# DMX_1_0.net
KiCad netlist of a schematic drawn in EAGLE
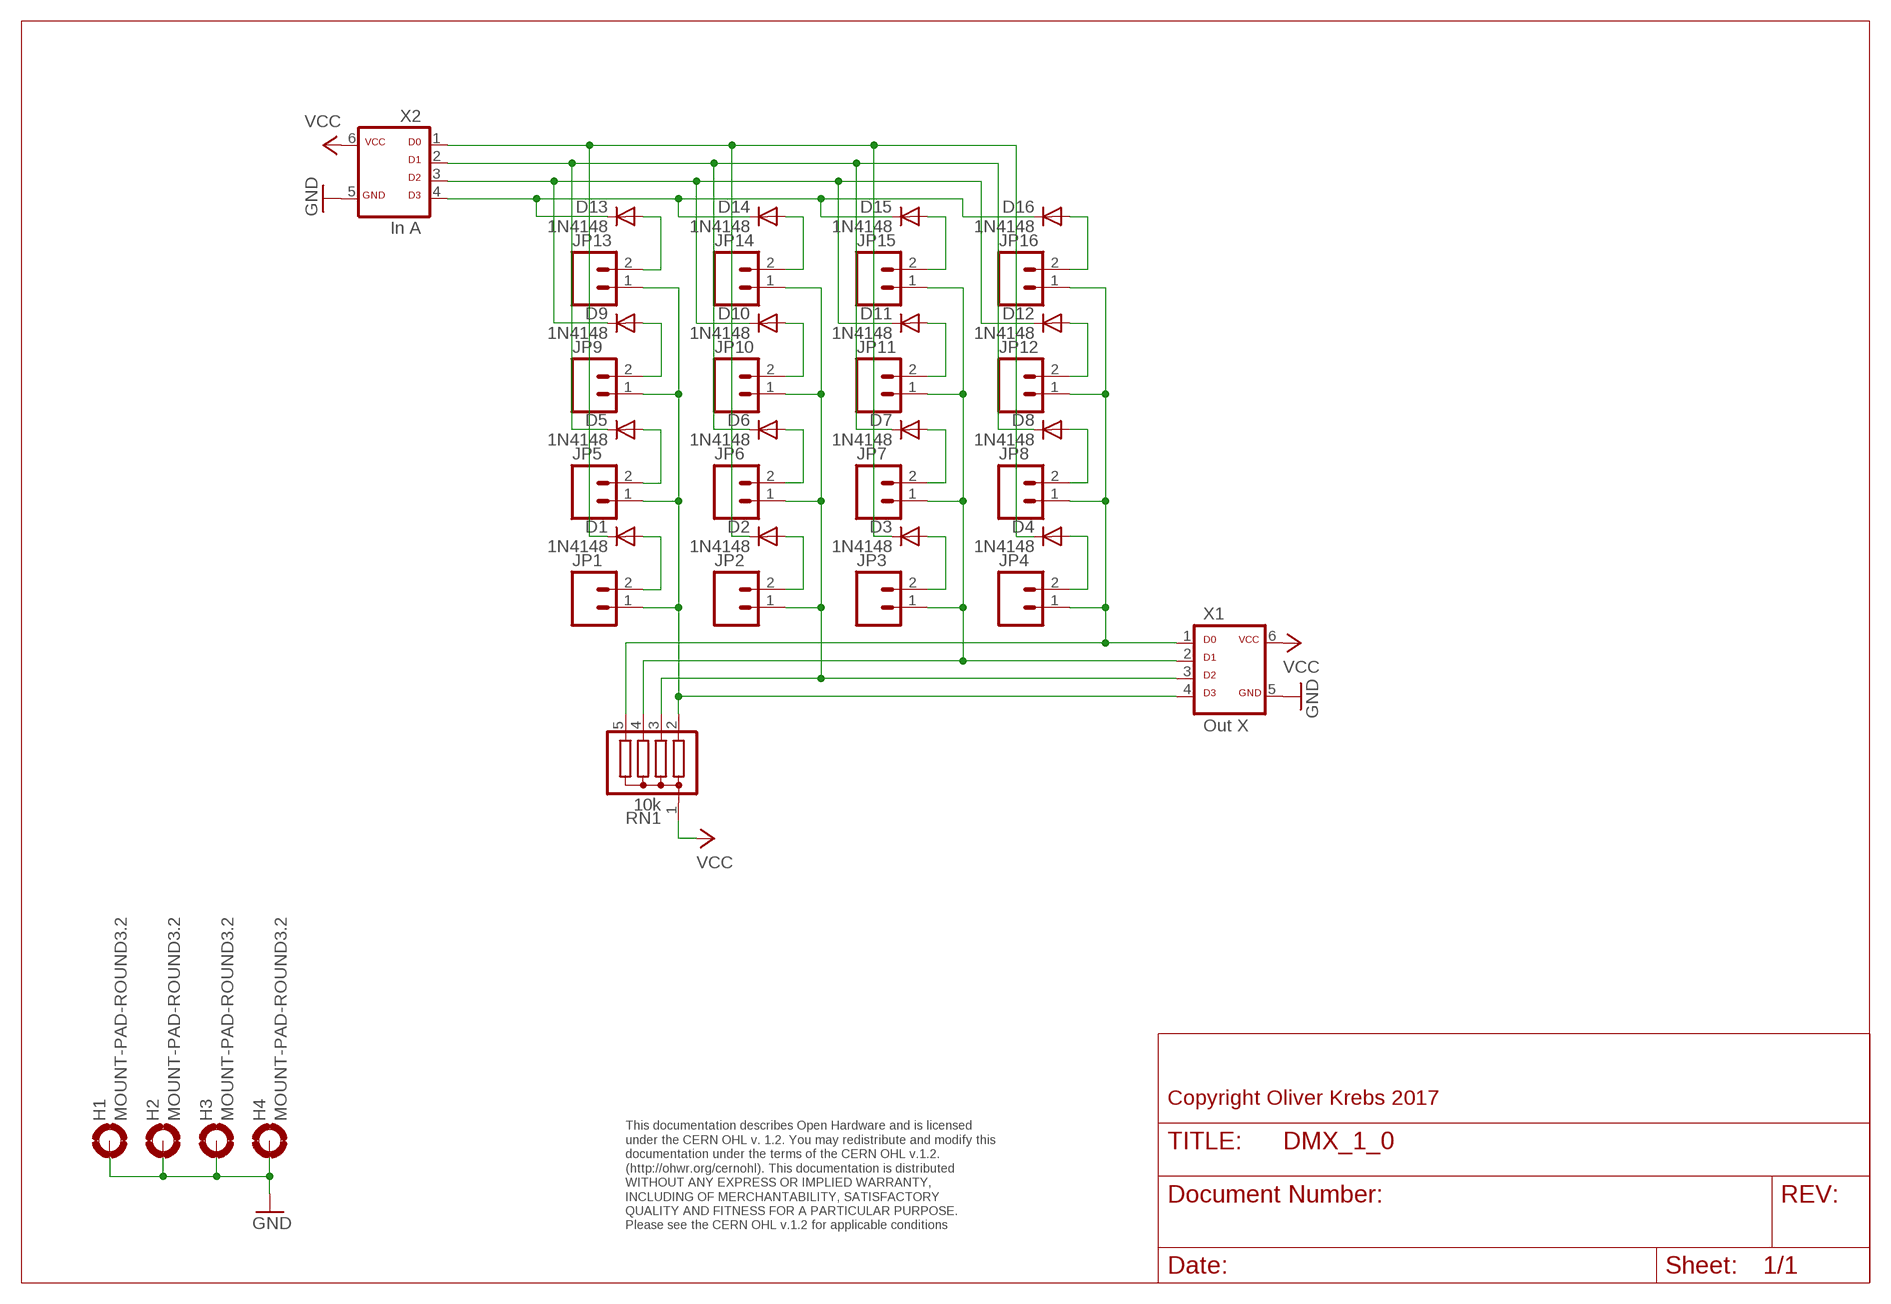
[diagram p0: schematic, sheet 1]

(export (version "E")
  (design (tool "Eeschema 10.0.6"))
  (components
    (comp (ref "D1")
      (value "1N4148")
      (footprint "eagle-import:DO35-7")
      (libsource (lib "eagle-import") (part "1N4148DO35-7"))
    )
    (comp (ref "D2")
      (value "1N4148")
      (footprint "eagle-import:DO35-7")
      (libsource (lib "eagle-import") (part "1N4148DO35-7"))
    )
    (comp (ref "D3")
      (value "1N4148")
      (footprint "eagle-import:DO35-7")
      (libsource (lib "eagle-import") (part "1N4148DO35-7"))
    )
    (comp (ref "D4")
      (value "1N4148")
      (footprint "eagle-import:DO35-7")
      (libsource (lib "eagle-import") (part "1N4148DO35-7"))
    )
    (comp (ref "D5")
      (value "1N4148")
      (footprint "eagle-import:DO35-7")
      (libsource (lib "eagle-import") (part "1N4148DO35-7"))
    )
    (comp (ref "D6")
      (value "1N4148")
      (footprint "eagle-import:DO35-7")
      (libsource (lib "eagle-import") (part "1N4148DO35-7"))
    )
    (comp (ref "D7")
      (value "1N4148")
      (footprint "eagle-import:DO35-7")
      (libsource (lib "eagle-import") (part "1N4148DO35-7"))
    )
    (comp (ref "D8")
      (value "1N4148")
      (footprint "eagle-import:DO35-7")
      (libsource (lib "eagle-import") (part "1N4148DO35-7"))
    )
    (comp (ref "D9")
      (value "1N4148")
      (footprint "eagle-import:DO35-7")
      (libsource (lib "eagle-import") (part "1N4148DO35-7"))
    )
    (comp (ref "D10")
      (value "1N4148")
      (footprint "eagle-import:DO35-7")
      (libsource (lib "eagle-import") (part "1N4148DO35-7"))
    )
    (comp (ref "D11")
      (value "1N4148")
      (footprint "eagle-import:DO35-7")
      (libsource (lib "eagle-import") (part "1N4148DO35-7"))
    )
    (comp (ref "D12")
      (value "1N4148")
      (footprint "eagle-import:DO35-7")
      (libsource (lib "eagle-import") (part "1N4148DO35-7"))
    )
    (comp (ref "D13")
      (value "1N4148")
      (footprint "eagle-import:DO35-7")
      (libsource (lib "eagle-import") (part "1N4148DO35-7"))
    )
    (comp (ref "D14")
      (value "1N4148")
      (footprint "eagle-import:DO35-7")
      (libsource (lib "eagle-import") (part "1N4148DO35-7"))
    )
    (comp (ref "D15")
      (value "1N4148")
      (footprint "eagle-import:DO35-7")
      (libsource (lib "eagle-import") (part "1N4148DO35-7"))
    )
    (comp (ref "D16")
      (value "1N4148")
      (footprint "eagle-import:DO35-7")
      (libsource (lib "eagle-import") (part "1N4148DO35-7"))
    )
    (comp (ref "H1")
      (value "MOUNT-PAD-ROUND3.2")
      (footprint "eagle-import:3,2-PAD")
      (libsource (lib "eagle-import") (part "MOUNT-PAD-ROUND3.2"))
    )
    (comp (ref "H2")
      (value "MOUNT-PAD-ROUND3.2")
      (footprint "eagle-import:3,2-PAD")
      (libsource (lib "eagle-import") (part "MOUNT-PAD-ROUND3.2"))
    )
    (comp (ref "H3")
      (value "MOUNT-PAD-ROUND3.2")
      (footprint "eagle-import:3,2-PAD")
      (libsource (lib "eagle-import") (part "MOUNT-PAD-ROUND3.2"))
    )
    (comp (ref "H4")
      (value "MOUNT-PAD-ROUND3.2")
      (footprint "eagle-import:3,2-PAD")
      (libsource (lib "eagle-import") (part "MOUNT-PAD-ROUND3.2"))
    )
    (comp (ref "JP1")
      (value "M02PTH")
      (footprint "eagle-import:1X02")
      (libsource (lib "eagle-import") (part "M02PTH"))
    )
    (comp (ref "JP2")
      (value "M02PTH")
      (footprint "eagle-import:1X02")
      (libsource (lib "eagle-import") (part "M02PTH"))
    )
    (comp (ref "JP3")
      (value "M02PTH")
      (footprint "eagle-import:1X02")
      (libsource (lib "eagle-import") (part "M02PTH"))
    )
    (comp (ref "JP4")
      (value "M02PTH")
      (footprint "eagle-import:1X02")
      (libsource (lib "eagle-import") (part "M02PTH"))
    )
    (comp (ref "JP5")
      (value "M02PTH")
      (footprint "eagle-import:1X02")
      (libsource (lib "eagle-import") (part "M02PTH"))
    )
    (comp (ref "JP6")
      (value "M02PTH")
      (footprint "eagle-import:1X02")
      (libsource (lib "eagle-import") (part "M02PTH"))
    )
    (comp (ref "JP7")
      (value "M02PTH")
      (footprint "eagle-import:1X02")
      (libsource (lib "eagle-import") (part "M02PTH"))
    )
    (comp (ref "JP8")
      (value "M02PTH")
      (footprint "eagle-import:1X02")
      (libsource (lib "eagle-import") (part "M02PTH"))
    )
    (comp (ref "JP9")
      (value "M02PTH")
      (footprint "eagle-import:1X02")
      (libsource (lib "eagle-import") (part "M02PTH"))
    )
    (comp (ref "JP10")
      (value "M02PTH")
      (footprint "eagle-import:1X02")
      (libsource (lib "eagle-import") (part "M02PTH"))
    )
    (comp (ref "JP11")
      (value "M02PTH")
      (footprint "eagle-import:1X02")
      (libsource (lib "eagle-import") (part "M02PTH"))
    )
    (comp (ref "JP12")
      (value "M02PTH")
      (footprint "eagle-import:1X02")
      (libsource (lib "eagle-import") (part "M02PTH"))
    )
    (comp (ref "JP13")
      (value "M02PTH")
      (footprint "eagle-import:1X02")
      (libsource (lib "eagle-import") (part "M02PTH"))
    )
    (comp (ref "JP14")
      (value "M02PTH")
      (footprint "eagle-import:1X02")
      (libsource (lib "eagle-import") (part "M02PTH"))
    )
    (comp (ref "JP15")
      (value "M02PTH")
      (footprint "eagle-import:1X02")
      (libsource (lib "eagle-import") (part "M02PTH"))
    )
    (comp (ref "JP16")
      (value "M02PTH")
      (footprint "eagle-import:1X02")
      (libsource (lib "eagle-import") (part "M02PTH"))
    )
    (comp (ref "RN1")
      (value "10k")
      (footprint "eagle-import:SIL5")
      (libsource (lib "eagle-import") (part "G04R"))
    )
    (comp (ref "X1")
      (value "Out X")
      (footprint "eagle-import:ML-6")
      (libsource (lib "eagle-import") (part "ML6D"))
    )
    (comp (ref "X2")
      (value "In A")
      (footprint "eagle-import:ML-6")
      (libsource (lib "eagle-import") (part "ML6D"))
    )
  )
  (nets
    (net (code "1") (name "GND") (class "Default")
      (node (ref "H1") (pin "B3,2") (pinfunction "MOUNT_B3,2") (pintype "passive"))
      (node (ref "H2") (pin "B3,2") (pinfunction "MOUNT_B3,2") (pintype "passive"))
      (node (ref "H3") (pin "B3,2") (pinfunction "MOUNT_B3,2") (pintype "passive"))
      (node (ref "H4") (pin "B3,2") (pinfunction "MOUNT_B3,2") (pintype "passive"))
      (node (ref "X1") (pin "5") (pinfunction "5_5") (pintype "passive"))
      (node (ref "X2") (pin "5") (pinfunction "5_5") (pintype "passive"))
    )
    (net (code "2") (name "Net-(D1-PadA)") (class "Default")
      (node (ref "D1") (pin "A") (pinfunction "A_A") (pintype "passive"))
      (node (ref "JP1") (pin "2") (pinfunction "2_2") (pintype "passive"))
    )
    (net (code "3") (name "Net-(D1-PadC)") (class "Default")
      (node (ref "D1") (pin "C") (pinfunction "C_C") (pintype "passive"))
      (node (ref "D2") (pin "C") (pinfunction "C_C") (pintype "passive"))
      (node (ref "D3") (pin "C") (pinfunction "C_C") (pintype "passive"))
      (node (ref "D4") (pin "C") (pinfunction "C_C") (pintype "passive"))
      (node (ref "X2") (pin "1") (pinfunction "1_1") (pintype "passive"))
    )
    (net (code "4") (name "Net-(D2-PadA)") (class "Default")
      (node (ref "D2") (pin "A") (pinfunction "A_A") (pintype "passive"))
      (node (ref "JP2") (pin "2") (pinfunction "2_2") (pintype "passive"))
    )
    (net (code "5") (name "Net-(D3-PadA)") (class "Default")
      (node (ref "D3") (pin "A") (pinfunction "A_A") (pintype "passive"))
      (node (ref "JP3") (pin "2") (pinfunction "2_2") (pintype "passive"))
    )
    (net (code "6") (name "Net-(D4-PadA)") (class "Default")
      (node (ref "D4") (pin "A") (pinfunction "A_A") (pintype "passive"))
      (node (ref "JP4") (pin "2") (pinfunction "2_2") (pintype "passive"))
    )
    (net (code "7") (name "Net-(D5-PadA)") (class "Default")
      (node (ref "D5") (pin "A") (pinfunction "A_A") (pintype "passive"))
      (node (ref "JP5") (pin "2") (pinfunction "2_2") (pintype "passive"))
    )
    (net (code "8") (name "Net-(D5-PadC)") (class "Default")
      (node (ref "D5") (pin "C") (pinfunction "C_C") (pintype "passive"))
      (node (ref "D6") (pin "C") (pinfunction "C_C") (pintype "passive"))
      (node (ref "D7") (pin "C") (pinfunction "C_C") (pintype "passive"))
      (node (ref "D8") (pin "C") (pinfunction "C_C") (pintype "passive"))
      (node (ref "X2") (pin "2") (pinfunction "2_2") (pintype "passive"))
    )
    (net (code "9") (name "Net-(D6-PadA)") (class "Default")
      (node (ref "D6") (pin "A") (pinfunction "A_A") (pintype "passive"))
      (node (ref "JP6") (pin "2") (pinfunction "2_2") (pintype "passive"))
    )
    (net (code "10") (name "Net-(D7-PadA)") (class "Default")
      (node (ref "D7") (pin "A") (pinfunction "A_A") (pintype "passive"))
      (node (ref "JP7") (pin "2") (pinfunction "2_2") (pintype "passive"))
    )
    (net (code "11") (name "Net-(D8-PadA)") (class "Default")
      (node (ref "D8") (pin "A") (pinfunction "A_A") (pintype "passive"))
      (node (ref "JP8") (pin "2") (pinfunction "2_2") (pintype "passive"))
    )
    (net (code "12") (name "Net-(D9-PadA)") (class "Default")
      (node (ref "D9") (pin "A") (pinfunction "A_A") (pintype "passive"))
      (node (ref "JP9") (pin "2") (pinfunction "2_2") (pintype "passive"))
    )
    (net (code "13") (name "Net-(D10-PadA)") (class "Default")
      (node (ref "D10") (pin "A") (pinfunction "A_A") (pintype "passive"))
      (node (ref "JP10") (pin "2") (pinfunction "2_2") (pintype "passive"))
    )
    (net (code "14") (name "Net-(D10-PadC)") (class "Default")
      (node (ref "D10") (pin "C") (pinfunction "C_C") (pintype "passive"))
      (node (ref "D11") (pin "C") (pinfunction "C_C") (pintype "passive"))
      (node (ref "D12") (pin "C") (pinfunction "C_C") (pintype "passive"))
      (node (ref "D9") (pin "C") (pinfunction "C_C") (pintype "passive"))
      (node (ref "X2") (pin "3") (pinfunction "3_3") (pintype "passive"))
    )
    (net (code "15") (name "Net-(D11-PadA)") (class "Default")
      (node (ref "D11") (pin "A") (pinfunction "A_A") (pintype "passive"))
      (node (ref "JP11") (pin "2") (pinfunction "2_2") (pintype "passive"))
    )
    (net (code "16") (name "Net-(D12-PadA)") (class "Default")
      (node (ref "D12") (pin "A") (pinfunction "A_A") (pintype "passive"))
      (node (ref "JP12") (pin "2") (pinfunction "2_2") (pintype "passive"))
    )
    (net (code "17") (name "Net-(D13-PadA)") (class "Default")
      (node (ref "D13") (pin "A") (pinfunction "A_A") (pintype "passive"))
      (node (ref "JP13") (pin "2") (pinfunction "2_2") (pintype "passive"))
    )
    (net (code "18") (name "Net-(D13-PadC)") (class "Default")
      (node (ref "D13") (pin "C") (pinfunction "C_C") (pintype "passive"))
      (node (ref "D14") (pin "C") (pinfunction "C_C") (pintype "passive"))
      (node (ref "D15") (pin "C") (pinfunction "C_C") (pintype "passive"))
      (node (ref "D16") (pin "C") (pinfunction "C_C") (pintype "passive"))
      (node (ref "X2") (pin "4") (pinfunction "4_4") (pintype "passive"))
    )
    (net (code "19") (name "Net-(D14-PadA)") (class "Default")
      (node (ref "D14") (pin "A") (pinfunction "A_A") (pintype "passive"))
      (node (ref "JP14") (pin "2") (pinfunction "2_2") (pintype "passive"))
    )
    (net (code "20") (name "Net-(D15-PadA)") (class "Default")
      (node (ref "D15") (pin "A") (pinfunction "A_A") (pintype "passive"))
      (node (ref "JP15") (pin "2") (pinfunction "2_2") (pintype "passive"))
    )
    (net (code "21") (name "Net-(D16-PadA)") (class "Default")
      (node (ref "D16") (pin "A") (pinfunction "A_A") (pintype "passive"))
      (node (ref "JP16") (pin "2") (pinfunction "2_2") (pintype "passive"))
    )
    (net (code "22") (name "Net-(JP1-Pad1)") (class "Default")
      (node (ref "JP1") (pin "1") (pinfunction "1_1") (pintype "passive"))
      (node (ref "JP13") (pin "1") (pinfunction "1_1") (pintype "passive"))
      (node (ref "JP5") (pin "1") (pinfunction "1_1") (pintype "passive"))
      (node (ref "JP9") (pin "1") (pinfunction "1_1") (pintype "passive"))
      (node (ref "RN1") (pin "2") (pinfunction "2_2") (pintype "passive"))
      (node (ref "X1") (pin "4") (pinfunction "4_4") (pintype "passive"))
    )
    (net (code "23") (name "Net-(JP10-Pad1)") (class "Default")
      (node (ref "JP10") (pin "1") (pinfunction "1_1") (pintype "passive"))
      (node (ref "JP14") (pin "1") (pinfunction "1_1") (pintype "passive"))
      (node (ref "JP2") (pin "1") (pinfunction "1_1") (pintype "passive"))
      (node (ref "JP6") (pin "1") (pinfunction "1_1") (pintype "passive"))
      (node (ref "RN1") (pin "3") (pinfunction "3_3") (pintype "passive"))
      (node (ref "X1") (pin "3") (pinfunction "3_3") (pintype "passive"))
    )
    (net (code "24") (name "Net-(JP11-Pad1)") (class "Default")
      (node (ref "JP11") (pin "1") (pinfunction "1_1") (pintype "passive"))
      (node (ref "JP15") (pin "1") (pinfunction "1_1") (pintype "passive"))
      (node (ref "JP3") (pin "1") (pinfunction "1_1") (pintype "passive"))
      (node (ref "JP7") (pin "1") (pinfunction "1_1") (pintype "passive"))
      (node (ref "RN1") (pin "4") (pinfunction "4_4") (pintype "passive"))
      (node (ref "X1") (pin "2") (pinfunction "2_2") (pintype "passive"))
    )
    (net (code "25") (name "Net-(JP12-Pad1)") (class "Default")
      (node (ref "JP12") (pin "1") (pinfunction "1_1") (pintype "passive"))
      (node (ref "JP16") (pin "1") (pinfunction "1_1") (pintype "passive"))
      (node (ref "JP4") (pin "1") (pinfunction "1_1") (pintype "passive"))
      (node (ref "JP8") (pin "1") (pinfunction "1_1") (pintype "passive"))
      (node (ref "RN1") (pin "5") (pinfunction "5_5") (pintype "passive"))
      (node (ref "X1") (pin "1") (pinfunction "1_1") (pintype "passive"))
    )
    (net (code "26") (name "VCC") (class "Default")
      (node (ref "RN1") (pin "1") (pinfunction "1_1") (pintype "passive"))
      (node (ref "X1") (pin "6") (pinfunction "6_6") (pintype "passive"))
      (node (ref "X2") (pin "6") (pinfunction "6_6") (pintype "passive"))
    )
  )
)
